# CombinedVentSchem.net
KiCad netlist of a schematic drawn in EAGLE
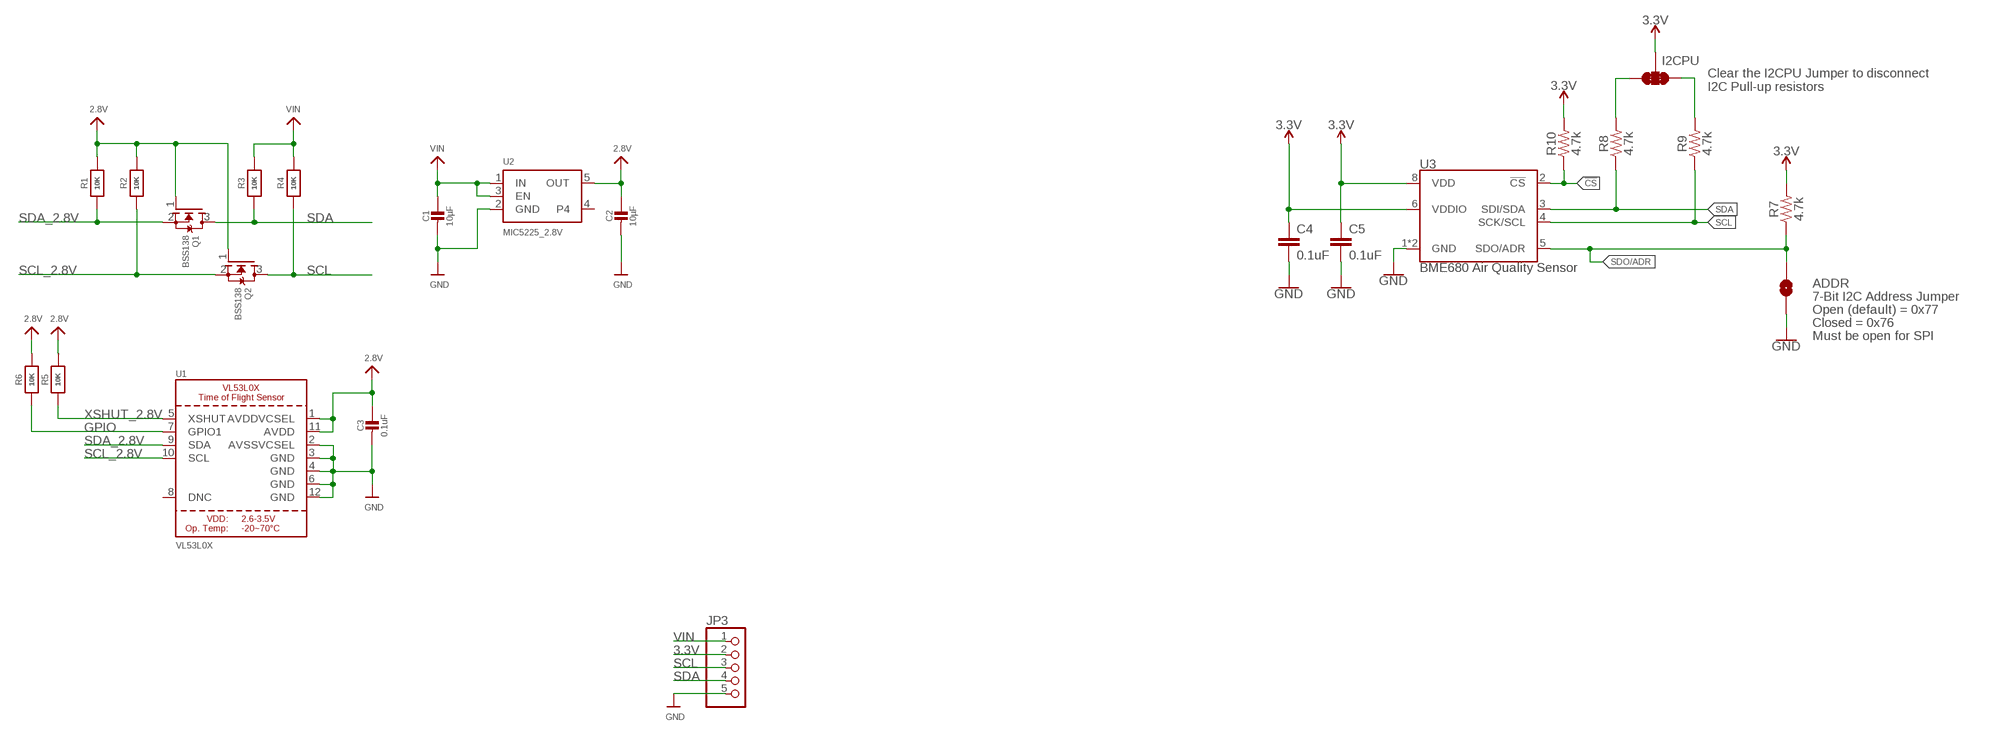
[diagram p0: schematic, sheet 1]

(export (version "E")
  (design (tool "Eeschema 10.0.6"))
  (components
    (comp (ref "ADDR")
      (value "JUMPER-SMT_2_NO_SILK")
      (footprint "eagle-import:SMT-JUMPER_2_NO_SILK")
      (libsource (lib "eagle-import") (part "JUMPER-SMT_2_NO_SILK"))
    )
    (comp (ref "C1")
      (value "10µF")
      (footprint "eagle-import:0805-NO")
      (libsource (lib "eagle-import") (part "CAP_CERAMIC0805-NOOUTLINE"))
    )
    (comp (ref "C2")
      (value "10µF")
      (footprint "eagle-import:0805-NO")
      (libsource (lib "eagle-import") (part "CAP_CERAMIC0805-NOOUTLINE"))
    )
    (comp (ref "C3")
      (value "0.1uF")
      (footprint "eagle-import:0805-NO")
      (libsource (lib "eagle-import") (part "CAP_CERAMIC0805-NOOUTLINE"))
    )
    (comp (ref "C4")
      (value "0.1uF")
      (footprint "eagle-import:0603")
      (libsource (lib "eagle-import") (part "0.1UF-0603-100V-10%"))
    )
    (comp (ref "C5")
      (value "0.1uF")
      (footprint "eagle-import:0603")
      (libsource (lib "eagle-import") (part "0.1UF-0603-100V-10%"))
    )
    (comp (ref "I2CPU")
      (value "I2C PU")
      (footprint "eagle-import:SMT-JUMPER_3_2-NC_TRACE_SILK")
      (libsource (lib "eagle-import") (part "JUMPER-SMT_3_2-NC_TRACE_SILK"))
    )
    (comp (ref "JP3")
      (value "PINHD-1X55X2MM")
      (footprint "eagle-import:1_05X2MM")
      (libsource (lib "eagle-import") (part "PINHD-1X55X2MM"))
    )
    (comp (ref "Q1")
      (value "BSS138")
      (footprint "eagle-import:SOT23-WIDE")
      (libsource (lib "eagle-import") (part "MOSFET-NWIDE"))
    )
    (comp (ref "Q2")
      (value "BSS138")
      (footprint "eagle-import:SOT23-WIDE")
      (libsource (lib "eagle-import") (part "MOSFET-NWIDE"))
    )
    (comp (ref "R1")
      (value "10K")
      (footprint "eagle-import:0805-NO")
      (libsource (lib "eagle-import") (part "RESISTOR0805_NOOUTLINE"))
    )
    (comp (ref "R2")
      (value "10K")
      (footprint "eagle-import:0805-NO")
      (libsource (lib "eagle-import") (part "RESISTOR0805_NOOUTLINE"))
    )
    (comp (ref "R3")
      (value "10K")
      (footprint "eagle-import:0805-NO")
      (libsource (lib "eagle-import") (part "RESISTOR0805_NOOUTLINE"))
    )
    (comp (ref "R4")
      (value "10K")
      (footprint "eagle-import:0805-NO")
      (libsource (lib "eagle-import") (part "RESISTOR0805_NOOUTLINE"))
    )
    (comp (ref "R5")
      (value "10K")
      (footprint "eagle-import:0805-NO")
      (libsource (lib "eagle-import") (part "RESISTOR0805_NOOUTLINE"))
    )
    (comp (ref "R6")
      (value "10K")
      (footprint "eagle-import:0805-NO")
      (libsource (lib "eagle-import") (part "RESISTOR0805_NOOUTLINE"))
    )
    (comp (ref "R7")
      (value "4.7k")
      (footprint "eagle-import:0603@1")
      (libsource (lib "eagle-import") (part "4.7KOHM-0603-1/10W-1%"))
    )
    (comp (ref "R8")
      (value "4.7k")
      (footprint "eagle-import:0603@1")
      (libsource (lib "eagle-import") (part "4.7KOHM-0603-1/10W-1%"))
    )
    (comp (ref "R9")
      (value "4.7k")
      (footprint "eagle-import:0603@1")
      (libsource (lib "eagle-import") (part "4.7KOHM-0603-1/10W-1%"))
    )
    (comp (ref "R10")
      (value "4.7k")
      (footprint "eagle-import:0603@1")
      (libsource (lib "eagle-import") (part "4.7KOHM-0603-1/10W-1%"))
    )
    (comp (ref "U1")
      (value "VL53L0X")
      (footprint "eagle-import:LGA12_ST")
      (libsource (lib "eagle-import") (part "VL53L0X"))
    )
    (comp (ref "U2")
      (value "MIC5225_2.8V")
      (footprint "eagle-import:SOT23-5")
      (libsource (lib "eagle-import") (part "VREG_SOT23-5"))
    )
    (comp (ref "U3")
      (value "BME680 Air Quality Sensor")
      (footprint "eagle-import:LGA3.0X3.0")
      (libsource (lib "eagle-import") (part "BME680-LGA"))
    )
  )
  (nets
    (net (code "1") (name "/GPIO") (class "Default")
      (node (ref "R6") (pin "1") (pinfunction "1_1") (pintype "passive"))
      (node (ref "U1") (pin "7") (pinfunction "GPIO1_7") (pintype "output"))
    )
    (net (code "2") (name "/SCL_2.8V") (class "Default")
      (node (ref "Q2") (pin "2") (pinfunction "S_2") (pintype "bidirectional"))
      (node (ref "R2") (pin "1") (pinfunction "1_1") (pintype "passive"))
      (node (ref "U1") (pin "10") (pinfunction "SCL_10") (pintype "open_collector"))
    )
    (net (code "3") (name "/SDA_2.8V") (class "Default")
      (node (ref "Q1") (pin "2") (pinfunction "S_2") (pintype "bidirectional"))
      (node (ref "R1") (pin "1") (pinfunction "1_1") (pintype "passive"))
      (node (ref "U1") (pin "9") (pinfunction "SDA_9") (pintype "open_collector"))
    )
    (net (code "4") (name "/XSHUT_2.8V") (class "Default")
      (node (ref "R5") (pin "1") (pinfunction "1_1") (pintype "passive"))
      (node (ref "U1") (pin "5") (pinfunction "XSHUT_5") (pintype "input"))
    )
    (net (code "5") (name "/~{CS}") (class "Default")
      (node (ref "R10") (pin "1") (pinfunction "1_1") (pintype "passive"))
      (node (ref "U3") (pin "2") (pinfunction "~{CS}_2") (pintype "bidirectional"))
    )
    (net (code "6") (name "2.8V") (class "Default")
      (node (ref "C2") (pin "1") (pinfunction "1_1") (pintype "passive"))
      (node (ref "C3") (pin "1") (pinfunction "1_1") (pintype "passive"))
      (node (ref "Q1") (pin "1") (pinfunction "G_1") (pintype "bidirectional"))
      (node (ref "Q2") (pin "1") (pinfunction "G_1") (pintype "bidirectional"))
      (node (ref "R1") (pin "2") (pinfunction "2_2") (pintype "passive"))
      (node (ref "R2") (pin "2") (pinfunction "2_2") (pintype "passive"))
      (node (ref "R5") (pin "2") (pinfunction "2_2") (pintype "passive"))
      (node (ref "R6") (pin "2") (pinfunction "2_2") (pintype "passive"))
      (node (ref "U1") (pin "1") (pinfunction "AVDDVCSEL_1") (pintype "power_in"))
      (node (ref "U1") (pin "11") (pinfunction "AVDD_11") (pintype "power_in"))
      (node (ref "U2") (pin "5") (pinfunction "OUT_5") (pintype "power_in"))
    )
    (net (code "7") (name "3.3V") (class "Default")
      (node (ref "C4") (pin "1") (pinfunction "1_1") (pintype "passive"))
      (node (ref "C5") (pin "1") (pinfunction "1_1") (pintype "passive"))
      (node (ref "I2CPU") (pin "2") (pinfunction "2_2") (pintype "passive"))
      (node (ref "JP3") (pin "2") (pinfunction "2_2") (pintype "passive"))
      (node (ref "R10") (pin "2") (pinfunction "2_2") (pintype "passive"))
      (node (ref "R7") (pin "2") (pinfunction "2_2") (pintype "passive"))
      (node (ref "U3") (pin "6") (pinfunction "VDDIO_6") (pintype "bidirectional"))
      (node (ref "U3") (pin "8") (pinfunction "VDD_8") (pintype "bidirectional"))
    )
    (net (code "8") (name "GND") (class "Default")
      (node (ref "ADDR") (pin "1") (pinfunction "1_1") (pintype "passive"))
      (node (ref "C1") (pin "2") (pinfunction "2_2") (pintype "passive"))
      (node (ref "C2") (pin "2") (pinfunction "2_2") (pintype "passive"))
      (node (ref "C3") (pin "2") (pinfunction "2_2") (pintype "passive"))
      (node (ref "C4") (pin "2") (pinfunction "2_2") (pintype "passive"))
      (node (ref "C5") (pin "2") (pinfunction "2_2") (pintype "passive"))
      (node (ref "JP3") (pin "5") (pinfunction "5_5") (pintype "passive"))
      (node (ref "U1") (pin "12") (pinfunction "GND_12") (pintype "power_in"))
      (node (ref "U1") (pin "2") (pinfunction "AVSSVCSEL_2") (pintype "power_in"))
      (node (ref "U1") (pin "3") (pinfunction "GND_3") (pintype "power_in"))
      (node (ref "U1") (pin "4") (pinfunction "GND_4") (pintype "power_in"))
      (node (ref "U1") (pin "6") (pinfunction "GND_6") (pintype "power_in"))
      (node (ref "U2") (pin "2") (pinfunction "GND_2") (pintype "power_in"))
      (node (ref "U3") (pin "1") (pinfunction "GND_1") (pintype "bidirectional"))
      (node (ref "U3") (pin "7") (pinfunction "GND_7") (pintype "bidirectional"))
    )
    (net (code "9") (name "Net-(I2CPU-Pad1)") (class "Default")
      (node (ref "I2CPU") (pin "1") (pinfunction "1_1") (pintype "passive"))
      (node (ref "R9") (pin "2") (pinfunction "2_2") (pintype "passive"))
    )
    (net (code "10") (name "Net-(I2CPU-Pad3)") (class "Default")
      (node (ref "I2CPU") (pin "3") (pinfunction "3_3") (pintype "passive"))
      (node (ref "R8") (pin "2") (pinfunction "2_2") (pintype "passive"))
    )
    (net (code "11") (name "SCL") (class "Default")
      (node (ref "JP3") (pin "3") (pinfunction "3_3") (pintype "passive"))
      (node (ref "Q2") (pin "3") (pinfunction "D_3") (pintype "bidirectional"))
      (node (ref "R4") (pin "1") (pinfunction "1_1") (pintype "passive"))
      (node (ref "R9") (pin "1") (pinfunction "1_1") (pintype "passive"))
      (node (ref "U3") (pin "4") (pinfunction "SCK/SCL_4") (pintype "bidirectional"))
    )
    (net (code "12") (name "SDA") (class "Default")
      (node (ref "JP3") (pin "4") (pinfunction "4_4") (pintype "passive"))
      (node (ref "Q1") (pin "3") (pinfunction "D_3") (pintype "bidirectional"))
      (node (ref "R3") (pin "1") (pinfunction "1_1") (pintype "passive"))
      (node (ref "R8") (pin "1") (pinfunction "1_1") (pintype "passive"))
      (node (ref "U3") (pin "3") (pinfunction "SDI/SDA_3") (pintype "bidirectional"))
    )
    (net (code "13") (name "SDO{slash}ADR") (class "Default")
      (node (ref "ADDR") (pin "2") (pinfunction "2_2") (pintype "passive"))
      (node (ref "R7") (pin "1") (pinfunction "1_1") (pintype "passive"))
      (node (ref "U3") (pin "5") (pinfunction "SDO/ADR_5") (pintype "bidirectional"))
    )
    (net (code "14") (name "VIN") (class "Default")
      (node (ref "C1") (pin "1") (pinfunction "1_1") (pintype "passive"))
      (node (ref "JP3") (pin "1") (pinfunction "1_1") (pintype "passive"))
      (node (ref "R3") (pin "2") (pinfunction "2_2") (pintype "passive"))
      (node (ref "R4") (pin "2") (pinfunction "2_2") (pintype "passive"))
      (node (ref "U2") (pin "1") (pinfunction "IN_1") (pintype "power_in"))
      (node (ref "U2") (pin "3") (pinfunction "EN_3") (pintype "input"))
    )
    (net (code "15") (name "unconnected-(U1-DNC-Pad8)") (class "Default")
      (node (ref "U1") (pin "8") (pinfunction "DNC_8") (pintype "no_connect"))
    )
    (net (code "16") (name "unconnected-(U2-P4-Pad4)") (class "Default")
      (node (ref "U2") (pin "4") (pinfunction "P4_4") (pintype "bidirectional"))
    )
  )
)
